# Gate_Driver_cct.net
KiCad netlist of a schematic drawn in Altium Designer
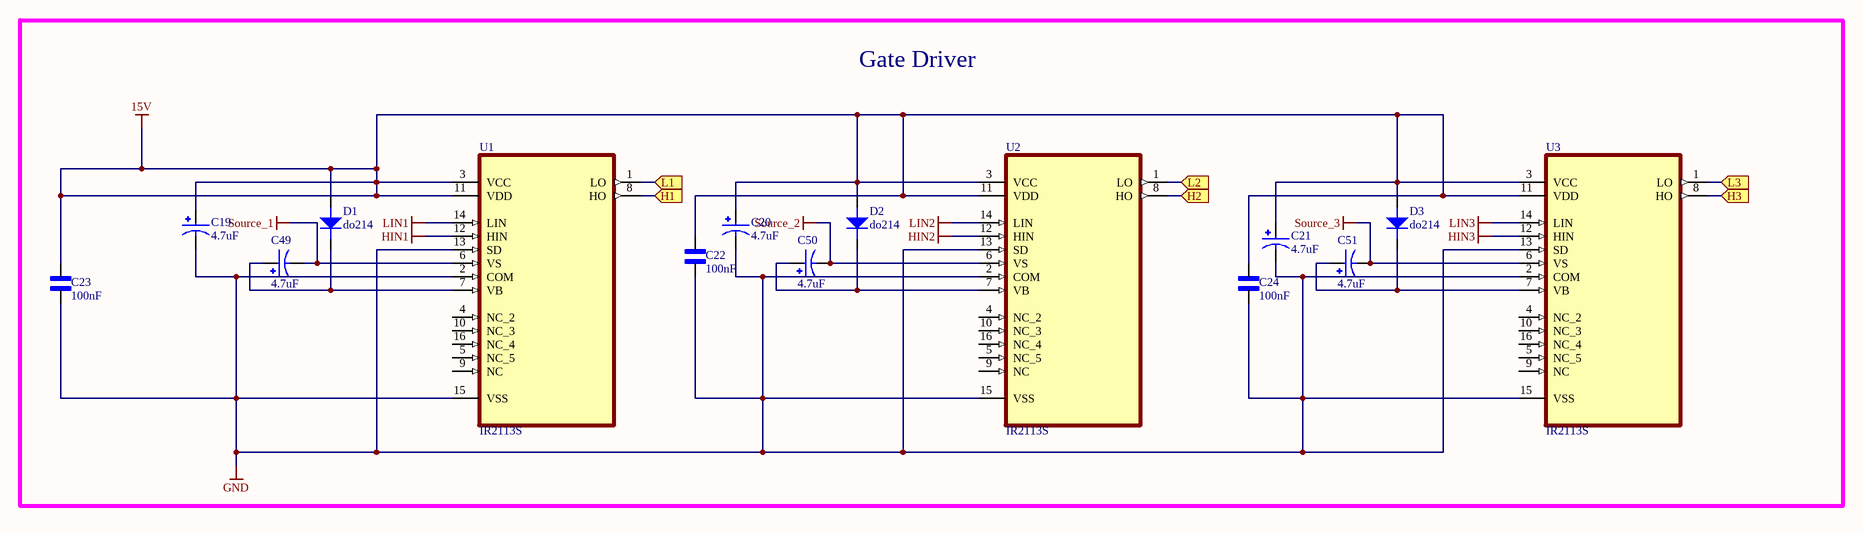
[diagram p0: Gate_Driver_cct.SchDoc]

(export (version "E")
  (design (tool "Eeschema 10.0.6"))
  (components
    (comp (ref "C19")
      (value "4.7uF")
      (footprint "CAP ALSMD POLY 4.3MM H5.5MM")
      (libsource (lib "PROJE") (part "CAP 4.7uF"))
    )
    (comp (ref "C20")
      (value "4.7uF")
      (footprint "CAP ALSMD POLY 4.3MM H5.5MM")
      (libsource (lib "PROJE") (part "CAP 4.7uF"))
    )
    (comp (ref "C21")
      (value "4.7uF")
      (footprint "CAP ALSMD POLY 4.3MM H5.5MM")
      (libsource (lib "PROJE") (part "CAP 4.7uF"))
    )
    (comp (ref "C22")
      (value "100nF")
      (footprint "C-0805W")
      (fields
        (field (name "MF") "Wurth Electronics Inc")
        (field (name "MP") "885012207098")
        (field (name "BUYPART") "https://www.snapeda.com/parts/885012207098/Wurth%20Electronics%20Inc/view-part/4217223/?ref=eda")
      )
      (libsource (lib "PROJE") (part "CAP 100nF 50V SMT 0805"))
    )
    (comp (ref "C23")
      (value "100nF")
      (footprint "C-0805W")
      (fields
        (field (name "MF") "Wurth Electronics Inc")
        (field (name "MP") "885012207098")
        (field (name "BUYPART") "https://www.snapeda.com/parts/885012207098/Wurth%20Electronics%20Inc/view-part/4217223/?ref=eda")
      )
      (libsource (lib "PROJE") (part "CAP 100nF 50V SMT 0805"))
    )
    (comp (ref "C24")
      (value "100nF")
      (footprint "C-0805W")
      (fields
        (field (name "MF") "Wurth Electronics Inc")
        (field (name "MP") "885012207098")
        (field (name "BUYPART") "https://www.snapeda.com/parts/885012207098/Wurth%20Electronics%20Inc/view-part/4217223/?ref=eda")
      )
      (libsource (lib "PROJE") (part "CAP 100nF 50V SMT 0805"))
    )
    (comp (ref "C49")
      (value "4.7uF")
      (footprint "CAP ALSMD POLY 4.3MM H5.5MM")
      (libsource (lib "") (part "CAP 4.7uF_1"))
    )
    (comp (ref "C50")
      (value "4.7uF")
      (footprint "CAP ALSMD POLY 4.3MM H5.5MM")
      (libsource (lib "") (part "CAP 4.7uF_1"))
    )
    (comp (ref "C51")
      (value "4.7uF")
      (footprint "CAP ALSMD POLY 4.3MM H5.5MM")
      (libsource (lib "") (part "CAP 4.7uF_1"))
    )
    (comp (ref "D1")
      (value "do214")
      (footprint "DO-214AC")
      (description "DIODE FAST SWITCHING Single 150mA 75V SMT SOD323")
      (libsource (lib "PROJE") (part "do214"))
    )
    (comp (ref "D2")
      (value "do214")
      (footprint "DO-214AC")
      (description "DIODE FAST SWITCHING Single 150mA 75V SMT SOD323")
      (libsource (lib "PROJE") (part "do214"))
    )
    (comp (ref "D3")
      (value "do214")
      (footprint "DO-214AC")
      (description "DIODE FAST SWITCHING Single 150mA 75V SMT SOD323")
      (libsource (lib "PROJE") (part "do214"))
    )
    (comp (ref "U1")
      (value "IR2113S")
      (footprint "SOIC127P1032X265-16N")
      (description "Half-Bridge Gate Driver IC Non-Inverting 16-SOIC")
      (fields (field (name "MF") "Infineon Technologies"))
      (libsource (lib "PROJE") (part "IR2113S"))
    )
    (comp (ref "U2")
      (value "IR2113S")
      (footprint "SOIC127P1032X265-16N")
      (description "Half-Bridge Gate Driver IC Non-Inverting 16-SOIC")
      (fields (field (name "MF") "Infineon Technologies"))
      (libsource (lib "PROJE") (part "IR2113S"))
    )
    (comp (ref "U3")
      (value "IR2113S")
      (footprint "SOIC127P1032X265-16N")
      (description "Half-Bridge Gate Driver IC Non-Inverting 16-SOIC")
      (fields (field (name "MF") "Infineon Technologies"))
      (libsource (lib "PROJE") (part "IR2113S"))
    )
  )
  (nets
    (net (code "1") (name "/H1") (class "Default")
      (node (ref "U1") (pin "8") (pinfunction "HO_8") (pintype "output"))
    )
    (net (code "2") (name "/H2") (class "Default")
      (node (ref "U2") (pin "8") (pinfunction "HO_8") (pintype "output"))
    )
    (net (code "3") (name "/H3") (class "Default")
      (node (ref "U3") (pin "8") (pinfunction "HO_8") (pintype "output"))
    )
    (net (code "4") (name "/L1") (class "Default")
      (node (ref "U1") (pin "1") (pinfunction "LO_1") (pintype "output"))
    )
    (net (code "5") (name "/L2") (class "Default")
      (node (ref "U2") (pin "1") (pinfunction "LO_1") (pintype "output"))
    )
    (net (code "6") (name "/L3") (class "Default")
      (node (ref "U3") (pin "1") (pinfunction "LO_1") (pintype "output"))
    )
    (net (code "7") (name "15V") (class "Default")
      (node (ref "C19") (pin "1") (pinfunction "1_1") (pintype "passive"))
      (node (ref "C20") (pin "1") (pinfunction "1_1") (pintype "passive"))
      (node (ref "C21") (pin "1") (pinfunction "1_1") (pintype "passive"))
      (node (ref "C22") (pin "1") (pinfunction "1_1") (pintype "passive"))
      (node (ref "C23") (pin "1") (pinfunction "1_1") (pintype "passive"))
      (node (ref "C24") (pin "1") (pinfunction "1_1") (pintype "passive"))
      (node (ref "D1") (pin "a") (pinfunction "a_a") (pintype "passive"))
      (node (ref "D2") (pin "a") (pinfunction "a_a") (pintype "passive"))
      (node (ref "D3") (pin "a") (pinfunction "a_a") (pintype "passive"))
      (node (ref "U1") (pin "11") (pinfunction "VDD_11") (pintype "power_in"))
      (node (ref "U1") (pin "3") (pinfunction "VCC_3") (pintype "power_in"))
      (node (ref "U2") (pin "11") (pinfunction "VDD_11") (pintype "power_in"))
      (node (ref "U2") (pin "3") (pinfunction "VCC_3") (pintype "power_in"))
      (node (ref "U3") (pin "11") (pinfunction "VDD_11") (pintype "power_in"))
      (node (ref "U3") (pin "3") (pinfunction "VCC_3") (pintype "power_in"))
    )
    (net (code "8") (name "GND") (class "Default")
      (node (ref "C19") (pin "2") (pinfunction "2_2") (pintype "passive"))
      (node (ref "C20") (pin "2") (pinfunction "2_2") (pintype "passive"))
      (node (ref "C21") (pin "2") (pinfunction "2_2") (pintype "passive"))
      (node (ref "C22") (pin "2") (pinfunction "2_2") (pintype "passive"))
      (node (ref "C23") (pin "2") (pinfunction "2_2") (pintype "passive"))
      (node (ref "C24") (pin "2") (pinfunction "2_2") (pintype "passive"))
      (node (ref "U1") (pin "13") (pinfunction "SD_13") (pintype "input"))
      (node (ref "U1") (pin "15") (pinfunction "VSS_15") (pintype "passive"))
      (node (ref "U1") (pin "2") (pinfunction "COM_2") (pintype "input"))
      (node (ref "U2") (pin "13") (pinfunction "SD_13") (pintype "input"))
      (node (ref "U2") (pin "15") (pinfunction "VSS_15") (pintype "passive"))
      (node (ref "U2") (pin "2") (pinfunction "COM_2") (pintype "input"))
      (node (ref "U3") (pin "13") (pinfunction "SD_13") (pintype "input"))
      (node (ref "U3") (pin "15") (pinfunction "VSS_15") (pintype "passive"))
      (node (ref "U3") (pin "2") (pinfunction "COM_2") (pintype "input"))
    )
    (net (code "9") (name "HIN1") (class "Default")
      (node (ref "U1") (pin "12") (pinfunction "HIN_12") (pintype "input"))
    )
    (net (code "10") (name "HIN2") (class "Default")
      (node (ref "U2") (pin "12") (pinfunction "HIN_12") (pintype "input"))
    )
    (net (code "11") (name "HIN3") (class "Default")
      (node (ref "U3") (pin "12") (pinfunction "HIN_12") (pintype "input"))
    )
    (net (code "12") (name "LIN1") (class "Default")
      (node (ref "U1") (pin "14") (pinfunction "LIN_14") (pintype "input"))
    )
    (net (code "13") (name "LIN2") (class "Default")
      (node (ref "U2") (pin "14") (pinfunction "LIN_14") (pintype "input"))
    )
    (net (code "14") (name "LIN3") (class "Default")
      (node (ref "U3") (pin "14") (pinfunction "LIN_14") (pintype "input"))
    )
    (net (code "15") (name "Net-(U1-VB)") (class "Default")
      (node (ref "C49") (pin "1") (pinfunction "1_1") (pintype "passive"))
      (node (ref "D1") (pin "k") (pinfunction "k_k") (pintype "passive"))
      (node (ref "U1") (pin "7") (pinfunction "VB_7") (pintype "input"))
    )
    (net (code "16") (name "Net-(U2-VB)") (class "Default")
      (node (ref "C50") (pin "1") (pinfunction "1_1") (pintype "passive"))
      (node (ref "D2") (pin "k") (pinfunction "k_k") (pintype "passive"))
      (node (ref "U2") (pin "7") (pinfunction "VB_7") (pintype "input"))
    )
    (net (code "17") (name "Net-(U3-VB)") (class "Default")
      (node (ref "C51") (pin "1") (pinfunction "1_1") (pintype "passive"))
      (node (ref "D3") (pin "k") (pinfunction "k_k") (pintype "passive"))
      (node (ref "U3") (pin "7") (pinfunction "VB_7") (pintype "input"))
    )
    (net (code "18") (name "Source_1") (class "Default")
      (node (ref "C49") (pin "2") (pinfunction "2_2") (pintype "passive"))
      (node (ref "U1") (pin "6") (pinfunction "VS_6") (pintype "input"))
    )
    (net (code "19") (name "Source_2") (class "Default")
      (node (ref "C50") (pin "2") (pinfunction "2_2") (pintype "passive"))
      (node (ref "U2") (pin "6") (pinfunction "VS_6") (pintype "input"))
    )
    (net (code "20") (name "Source_3") (class "Default")
      (node (ref "C51") (pin "2") (pinfunction "2_2") (pintype "passive"))
      (node (ref "U3") (pin "6") (pinfunction "VS_6") (pintype "input"))
    )
    (net (code "21") (name "unconnected-(U1-NC-Pad9)") (class "Default")
      (node (ref "U1") (pin "9") (pinfunction "NC_9") (pintype "input"))
    )
    (net (code "22") (name "unconnected-(U1-NC_2-Pad4)") (class "Default")
      (node (ref "U1") (pin "4") (pinfunction "NC_2_4") (pintype "input"))
    )
    (net (code "23") (name "unconnected-(U1-NC_3-Pad10)") (class "Default")
      (node (ref "U1") (pin "10") (pinfunction "NC_3_10") (pintype "input"))
    )
    (net (code "24") (name "unconnected-(U1-NC_4-Pad16)") (class "Default")
      (node (ref "U1") (pin "16") (pinfunction "NC_4_16") (pintype "input"))
    )
    (net (code "25") (name "unconnected-(U1-NC_5-Pad5)") (class "Default")
      (node (ref "U1") (pin "5") (pinfunction "NC_5_5") (pintype "input"))
    )
    (net (code "26") (name "unconnected-(U2-NC-Pad9)") (class "Default")
      (node (ref "U2") (pin "9") (pinfunction "NC_9") (pintype "input"))
    )
    (net (code "27") (name "unconnected-(U2-NC_2-Pad4)") (class "Default")
      (node (ref "U2") (pin "4") (pinfunction "NC_2_4") (pintype "input"))
    )
    (net (code "28") (name "unconnected-(U2-NC_3-Pad10)") (class "Default")
      (node (ref "U2") (pin "10") (pinfunction "NC_3_10") (pintype "input"))
    )
    (net (code "29") (name "unconnected-(U2-NC_4-Pad16)") (class "Default")
      (node (ref "U2") (pin "16") (pinfunction "NC_4_16") (pintype "input"))
    )
    (net (code "30") (name "unconnected-(U2-NC_5-Pad5)") (class "Default")
      (node (ref "U2") (pin "5") (pinfunction "NC_5_5") (pintype "input"))
    )
    (net (code "31") (name "unconnected-(U3-NC-Pad9)") (class "Default")
      (node (ref "U3") (pin "9") (pinfunction "NC_9") (pintype "input"))
    )
    (net (code "32") (name "unconnected-(U3-NC_2-Pad4)") (class "Default")
      (node (ref "U3") (pin "4") (pinfunction "NC_2_4") (pintype "input"))
    )
    (net (code "33") (name "unconnected-(U3-NC_3-Pad10)") (class "Default")
      (node (ref "U3") (pin "10") (pinfunction "NC_3_10") (pintype "input"))
    )
    (net (code "34") (name "unconnected-(U3-NC_4-Pad16)") (class "Default")
      (node (ref "U3") (pin "16") (pinfunction "NC_4_16") (pintype "input"))
    )
    (net (code "35") (name "unconnected-(U3-NC_5-Pad5)") (class "Default")
      (node (ref "U3") (pin "5") (pinfunction "NC_5_5") (pintype "input"))
    )
  )
)
